# SERIAL_FMU3_REV_G.net
KiCad netlist of a schematic drawn in Altium Designer
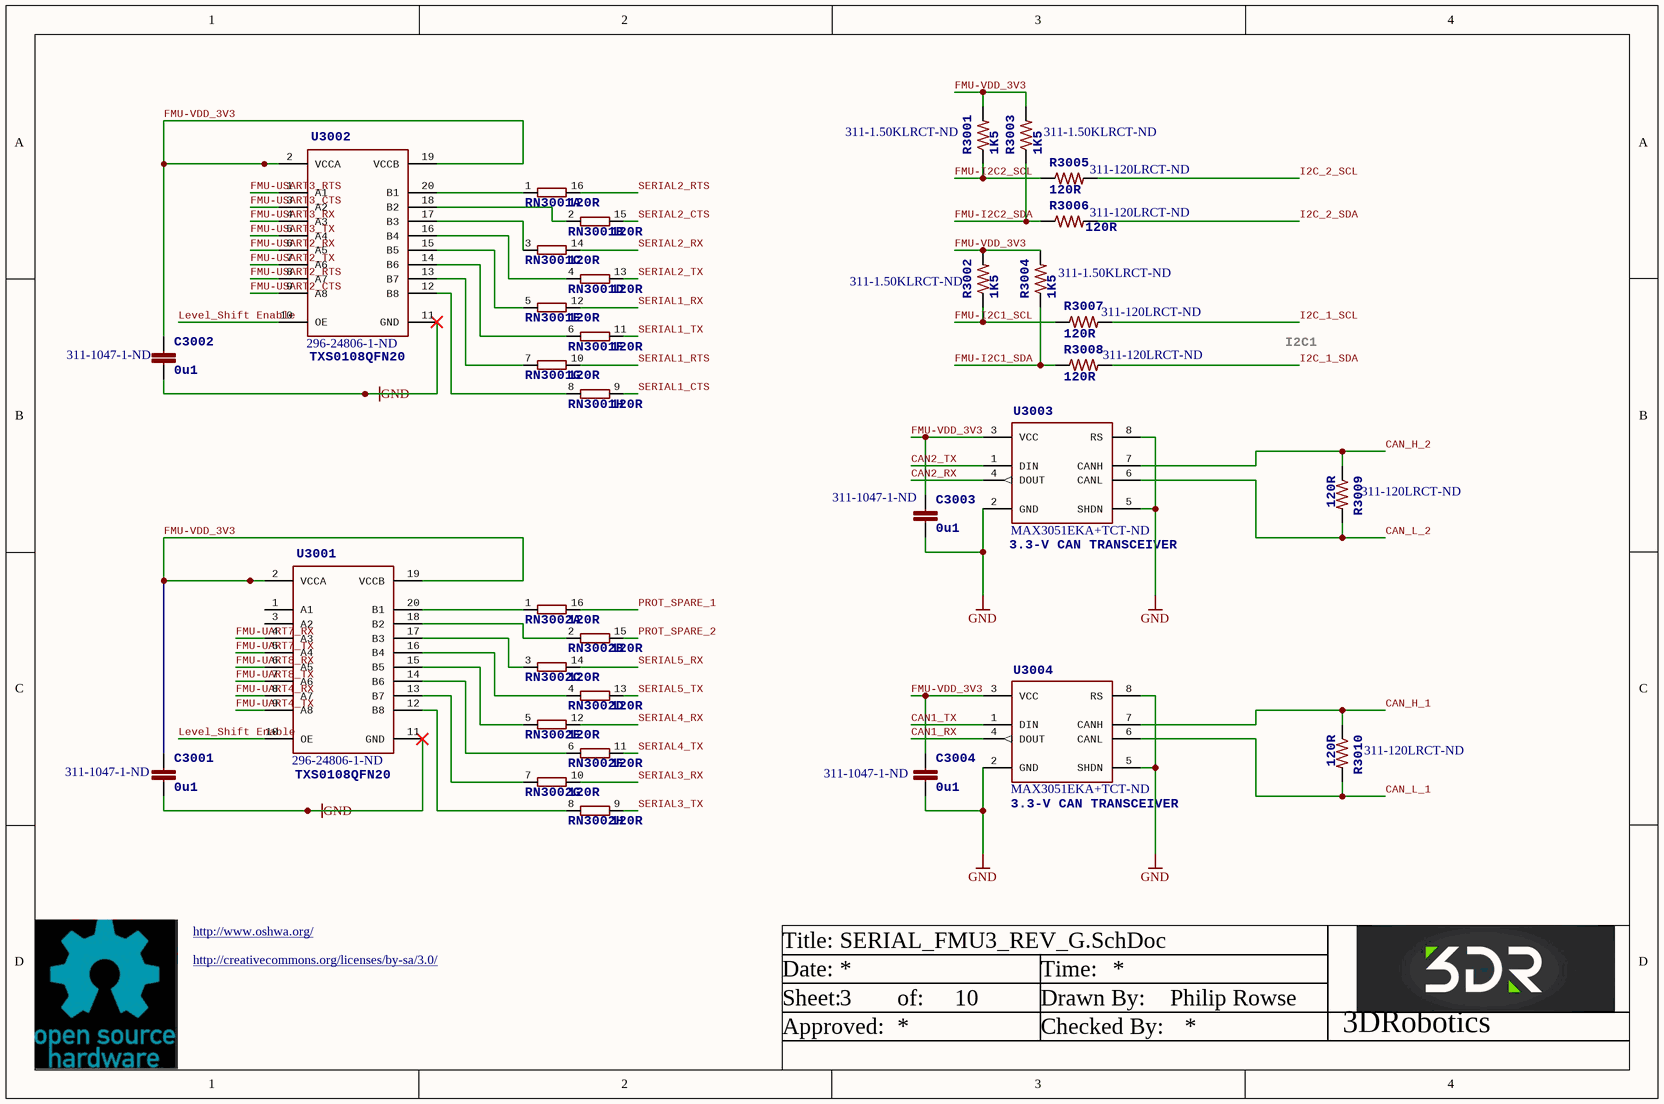
[diagram p0: SERIAL_FMU3_REV_G.SchDoc]

(export (version "E")
  (design (tool "Eeschema 10.0.6"))
  (components
    (comp (ref "C3001")
      (value "0u1")
      (footprint "0402-CAP")
      (description "CAP CER 0.1UF 16V Y5V 0402")
      (fields
        (field (name "PARTNO") "CC0402ZRY5V7BB104")
        (field (name "SUPPLIER PART NUMBER 1") "311-1047-1-ND")
        (field (name "3DR_PARTNO") "ECM0700")
      )
      (libsource (lib "pixhawk2") (part "CAP0402"))
    )
    (comp (ref "C3002")
      (value "0u1")
      (footprint "0402-CAP")
      (description "CAP CER 0.1UF 16V Y5V 0402")
      (fields
        (field (name "PARTNO") "CC0402ZRY5V7BB104")
        (field (name "SUPPLIER PART NUMBER 1") "311-1047-1-ND")
        (field (name "3DR_PARTNO") "ECM0700")
      )
      (libsource (lib "pixhawk2") (part "CAP0402"))
    )
    (comp (ref "C3003")
      (value "0u1")
      (footprint "0402-CAP")
      (description "CAP CER 0.1UF 16V Y5V 0402")
      (fields
        (field (name "PARTNO") "CC0402ZRY5V7BB104")
        (field (name "SUPPLIER PART NUMBER 1") "311-1047-1-ND")
        (field (name "3DR_PARTNO") "ECM0700")
      )
      (libsource (lib "pixhawk2") (part "CAP0402"))
    )
    (comp (ref "C3004")
      (value "0u1")
      (footprint "0402-CAP")
      (description "CAP CER 0.1UF 16V Y5V 0402")
      (fields
        (field (name "PARTNO") "CC0402ZRY5V7BB104")
        (field (name "SUPPLIER PART NUMBER 1") "311-1047-1-ND")
        (field (name "3DR_PARTNO") "ECM0700")
      )
      (libsource (lib "pixhawk2") (part "CAP0402"))
    )
    (comp (ref "R3001")
      (value "1K5")
      (footprint "0402-RES")
      (description "RES 1.5K OHM 1/16W 1% 0402 SMD")
      (fields
        (field (name "PARTNO") "RC0402FR-071K5L")
        (field (name "SUPPLIER PART NUMBER 1") "311-1.50KLRCT-ND")
        (field (name "3DR_PARTNO") "ECM0803")
      )
      (libsource (lib "pixhawk2") (part "RESISTOR0402-RES"))
    )
    (comp (ref "R3002")
      (value "1K5")
      (footprint "0402-RES")
      (description "RES 1.5K OHM 1/16W 1% 0402 SMD")
      (fields
        (field (name "PARTNO") "RC0402FR-071K5L")
        (field (name "SUPPLIER PART NUMBER 1") "311-1.50KLRCT-ND")
        (field (name "3DR_PARTNO") "ECM0803")
      )
      (libsource (lib "pixhawk2") (part "RESISTOR0402-RES"))
    )
    (comp (ref "R3003")
      (value "1K5")
      (footprint "0402-RES")
      (description "RES 1.5K OHM 1/16W 1% 0402 SMD")
      (fields
        (field (name "PARTNO") "RC0402FR-071K5L")
        (field (name "SUPPLIER PART NUMBER 1") "311-1.50KLRCT-ND")
        (field (name "3DR_PARTNO") "ECM0803")
      )
      (libsource (lib "pixhawk2") (part "RESISTOR0402-RES"))
    )
    (comp (ref "R3004")
      (value "1K5")
      (footprint "0402-RES")
      (description "RES 1.5K OHM 1/16W 1% 0402 SMD")
      (fields
        (field (name "PARTNO") "RC0402FR-071K5L")
        (field (name "SUPPLIER PART NUMBER 1") "311-1.50KLRCT-ND")
        (field (name "3DR_PARTNO") "ECM0803")
      )
      (libsource (lib "pixhawk2") (part "RESISTOR0402-RES"))
    )
    (comp (ref "R3005")
      (value "120R")
      (footprint "0402-RES")
      (description "RES 120 OHM 1/16W 1% 0402 SMD")
      (fields
        (field (name "PARTNO") "RC0402FR-07120RL")
        (field (name "SUPPLIER PART NUMBER 1") "311-120LRCT-ND")
        (field (name "3DR_PARTNO") "ECM0820")
      )
      (libsource (lib "pixhawk2") (part "RESISTOR0402-RES"))
    )
    (comp (ref "R3006")
      (value "120R")
      (footprint "0402-RES")
      (description "RES 120 OHM 1/16W 1% 0402 SMD")
      (fields
        (field (name "PARTNO") "RC0402FR-07120RL")
        (field (name "SUPPLIER PART NUMBER 1") "311-120LRCT-ND")
        (field (name "3DR_PARTNO") "ECM0820")
      )
      (libsource (lib "pixhawk2") (part "RESISTOR0402-RES"))
    )
    (comp (ref "R3007")
      (value "120R")
      (footprint "0402-RES")
      (description "RES 120 OHM 1/16W 1% 0402 SMD")
      (fields
        (field (name "PARTNO") "RC0402FR-07120RL")
        (field (name "SUPPLIER PART NUMBER 1") "311-120LRCT-ND")
        (field (name "3DR_PARTNO") "ECM0820")
      )
      (libsource (lib "pixhawk2") (part "RESISTOR0402-RES"))
    )
    (comp (ref "R3008")
      (value "120R")
      (footprint "0402-RES")
      (description "RES 120 OHM 1/16W 1% 0402 SMD")
      (fields
        (field (name "PARTNO") "RC0402FR-07120RL")
        (field (name "SUPPLIER PART NUMBER 1") "311-120LRCT-ND")
        (field (name "3DR_PARTNO") "ECM0820")
      )
      (libsource (lib "pixhawk2") (part "RESISTOR0402-RES"))
    )
    (comp (ref "R3009")
      (value "120R")
      (footprint "0402-RES")
      (description "RES 120 OHM 1/16W 1% 0402 SMD")
      (fields
        (field (name "PARTNO") "RC0402FR-07120RL")
        (field (name "SUPPLIER PART NUMBER 1") "311-120LRCT-ND")
        (field (name "3DR_PARTNO") "ECM0820")
      )
      (libsource (lib "pixhawk2") (part "RESISTOR0402-RES"))
    )
    (comp (ref "R3010")
      (value "120R")
      (footprint "0402-RES")
      (description "RES 120 OHM 1/16W 1% 0402 SMD")
      (fields
        (field (name "PARTNO") "RC0402FR-07120RL")
        (field (name "SUPPLIER PART NUMBER 1") "311-120LRCT-ND")
        (field (name "3DR_PARTNO") "ECM0820")
      )
      (libsource (lib "pixhawk2") (part "RESISTOR0402-RES"))
    )
    (comp (ref "RN3001")
      (value "120R")
      (footprint "EXB2HV")
      (description "RES ARRAY 120 OHM 8 RES 1506")
      (fields (field (name "PARTNO") "EXB-2HV121JV") (field (name "3DR_PARTNO") "EMC"))
      (libsource (lib "pixhawk2") (part "8R-NEXB2HV-120R"))
    )
    (comp (ref "RN3002")
      (value "120R")
      (footprint "EXB2HV")
      (description "RES ARRAY 120 OHM 8 RES 1506")
      (fields (field (name "PARTNO") "EXB-2HV121JV") (field (name "3DR_PARTNO") "EMC"))
      (libsource (lib "pixhawk2") (part "8R-NEXB2HV-120R"))
    )
    (comp (ref "U3001")
      (value "TXS0108QFN20")
      (footprint "QFN20-RGY")
      (description "IC XLATR VOLT-LVL 8B BDIR 20QFN")
      (fields
        (field (name "SUPPLIER PART NUMBER 1") "296-24806-1-ND")
        (field (name "3DR_PARTNO") "ECM0845")
        (field (name "PARTNO") "TXS0108ERGYR")
      )
      (libsource (lib "pixhawk2") (part "TXS0108QFN20"))
    )
    (comp (ref "U3002")
      (value "TXS0108QFN20")
      (footprint "QFN20-RGY")
      (description "IC XLATR VOLT-LVL 8B BDIR 20QFN")
      (fields
        (field (name "SUPPLIER PART NUMBER 1") "296-24806-1-ND")
        (field (name "3DR_PARTNO") "ECM0845")
        (field (name "PARTNO") "TXS0108ERGYR")
      )
      (libsource (lib "pixhawk2") (part "TXS0108QFN20"))
    )
    (comp (ref "U3003")
      (value "3.3-V CAN TRANSCEIVER")
      (footprint "SOT23-8")
      (description "IC TXRX CAN 1MBPS SOT23-8")
      (fields
        (field (name "SUPPLIER PART NUMBER 1") "MAX3051EKA+TCT-ND")
        (field (name "3DR_PARTNO") "ECM0831")
        (field (name "PARTNO") "MAX3051EKA+T")
      )
      (libsource (lib "pixhawk2") (part "MAX3051MAX3051EKA"))
    )
    (comp (ref "U3004")
      (value "3.3-V CAN TRANSCEIVER")
      (footprint "SOT23-8")
      (description "IC TXRX CAN 1MBPS SOT23-8")
      (fields
        (field (name "SUPPLIER PART NUMBER 1") "MAX3051EKA+TCT-ND")
        (field (name "3DR_PARTNO") "ECM0831")
        (field (name "PARTNO") "MAX3051EKA+T")
      )
      (libsource (lib "pixhawk2") (part "MAX3051MAX3051EKA"))
    )
  )
  (nets
    (net (code "1") (name "/CAN1_RX") (class "Default")
      (node (ref "U3004") (pin "4") (pinfunction "DOUT_4") (pintype "output"))
    )
    (net (code "2") (name "/CAN1_TX") (class "Default")
      (node (ref "U3004") (pin "1") (pinfunction "DIN_1") (pintype "passive"))
    )
    (net (code "3") (name "/CAN2_RX") (class "Default")
      (node (ref "U3003") (pin "4") (pinfunction "DOUT_4") (pintype "output"))
    )
    (net (code "4") (name "/CAN2_TX") (class "Default")
      (node (ref "U3003") (pin "1") (pinfunction "DIN_1") (pintype "passive"))
    )
    (net (code "5") (name "/CAN_H_1") (class "Default")
      (node (ref "R3010") (pin "P$1") (pinfunction "1_P$1") (pintype "passive"))
      (node (ref "U3004") (pin "7") (pinfunction "CANH_7") (pintype "passive"))
    )
    (net (code "6") (name "/CAN_H_2") (class "Default")
      (node (ref "R3009") (pin "P$1") (pinfunction "1_P$1") (pintype "passive"))
      (node (ref "U3003") (pin "7") (pinfunction "CANH_7") (pintype "passive"))
    )
    (net (code "7") (name "/CAN_L_1") (class "Default")
      (node (ref "R3010") (pin "P$2") (pinfunction "2_P$2") (pintype "passive"))
      (node (ref "U3004") (pin "6") (pinfunction "CANL_6") (pintype "passive"))
    )
    (net (code "8") (name "/CAN_L_2") (class "Default")
      (node (ref "R3009") (pin "P$2") (pinfunction "2_P$2") (pintype "passive"))
      (node (ref "U3003") (pin "6") (pinfunction "CANL_6") (pintype "passive"))
    )
    (net (code "9") (name "/FMU-I2C1_SCL") (class "Default")
      (node (ref "R3002") (pin "P$1") (pinfunction "1_P$1") (pintype "passive"))
      (node (ref "R3007") (pin "P$1") (pinfunction "1_P$1") (pintype "passive"))
    )
    (net (code "10") (name "/FMU-I2C1_SDA") (class "Default")
      (node (ref "R3004") (pin "P$1") (pinfunction "1_P$1") (pintype "passive"))
      (node (ref "R3008") (pin "P$1") (pinfunction "1_P$1") (pintype "passive"))
    )
    (net (code "11") (name "/FMU-I2C2_SCL") (class "Default")
      (node (ref "R3001") (pin "P$1") (pinfunction "1_P$1") (pintype "passive"))
      (node (ref "R3005") (pin "P$1") (pinfunction "1_P$1") (pintype "passive"))
    )
    (net (code "12") (name "/FMU-I2C2_SDA") (class "Default")
      (node (ref "R3003") (pin "P$1") (pinfunction "1_P$1") (pintype "passive"))
      (node (ref "R3006") (pin "P$1") (pinfunction "1_P$1") (pintype "passive"))
    )
    (net (code "13") (name "/FMU-UART4_RX") (class "Default")
      (node (ref "U3001") (pin "8") (pinfunction "A7_8") (pintype "passive"))
    )
    (net (code "14") (name "/FMU-UART4_TX") (class "Default")
      (node (ref "U3001") (pin "9") (pinfunction "A8_9") (pintype "passive"))
    )
    (net (code "15") (name "/FMU-UART7_RX") (class "Default")
      (node (ref "U3001") (pin "4") (pinfunction "A3_4") (pintype "passive"))
    )
    (net (code "16") (name "/FMU-UART7_TX") (class "Default")
      (node (ref "U3001") (pin "5") (pinfunction "A4_5") (pintype "passive"))
    )
    (net (code "17") (name "/FMU-UART8_RX") (class "Default")
      (node (ref "U3001") (pin "6") (pinfunction "A5_6") (pintype "passive"))
    )
    (net (code "18") (name "/FMU-UART8_TX") (class "Default")
      (node (ref "U3001") (pin "7") (pinfunction "A6_7") (pintype "passive"))
    )
    (net (code "19") (name "/FMU-USART2_CTS") (class "Default")
      (node (ref "U3002") (pin "9") (pinfunction "A8_9") (pintype "passive"))
    )
    (net (code "20") (name "/FMU-USART2_RTS") (class "Default")
      (node (ref "U3002") (pin "8") (pinfunction "A7_8") (pintype "passive"))
    )
    (net (code "21") (name "/FMU-USART2_RX") (class "Default")
      (node (ref "U3002") (pin "6") (pinfunction "A5_6") (pintype "passive"))
    )
    (net (code "22") (name "/FMU-USART2_TX") (class "Default")
      (node (ref "U3002") (pin "7") (pinfunction "A6_7") (pintype "passive"))
    )
    (net (code "23") (name "/FMU-USART3_CTS") (class "Default")
      (node (ref "U3002") (pin "3") (pinfunction "A2_3") (pintype "passive"))
    )
    (net (code "24") (name "/FMU-USART3_RTS") (class "Default")
      (node (ref "U3002") (pin "1") (pinfunction "A1_1") (pintype "passive"))
    )
    (net (code "25") (name "/FMU-USART3_RX") (class "Default")
      (node (ref "U3002") (pin "4") (pinfunction "A3_4") (pintype "passive"))
    )
    (net (code "26") (name "/FMU-USART3_TX") (class "Default")
      (node (ref "U3002") (pin "5") (pinfunction "A4_5") (pintype "passive"))
    )
    (net (code "27") (name "/FMU-VDD_3V3") (class "Default")
      (node (ref "C3001") (pin "P$1") (pinfunction "1_P$1") (pintype "passive"))
      (node (ref "C3002") (pin "P$1") (pinfunction "1_P$1") (pintype "passive"))
      (node (ref "C3003") (pin "P$1") (pinfunction "1_P$1") (pintype "passive"))
      (node (ref "C3004") (pin "P$1") (pinfunction "1_P$1") (pintype "passive"))
      (node (ref "R3001") (pin "P$2") (pinfunction "2_P$2") (pintype "passive"))
      (node (ref "R3002") (pin "P$2") (pinfunction "2_P$2") (pintype "passive"))
      (node (ref "R3003") (pin "P$2") (pinfunction "2_P$2") (pintype "passive"))
      (node (ref "R3004") (pin "P$2") (pinfunction "2_P$2") (pintype "passive"))
      (node (ref "U3001") (pin "19") (pinfunction "VCCB_19") (pintype "passive"))
      (node (ref "U3001") (pin "2") (pinfunction "VCCA_2") (pintype "passive"))
      (node (ref "U3002") (pin "19") (pinfunction "VCCB_19") (pintype "passive"))
      (node (ref "U3002") (pin "2") (pinfunction "VCCA_2") (pintype "passive"))
      (node (ref "U3003") (pin "3") (pinfunction "VCC_3") (pintype "passive"))
      (node (ref "U3004") (pin "3") (pinfunction "VCC_3") (pintype "passive"))
    )
    (net (code "28") (name "/I2C_1_SCL") (class "Default")
      (node (ref "R3007") (pin "P$2") (pinfunction "2_P$2") (pintype "passive"))
    )
    (net (code "29") (name "/I2C_1_SDA") (class "Default")
      (node (ref "R3008") (pin "P$2") (pinfunction "2_P$2") (pintype "passive"))
    )
    (net (code "30") (name "/I2C_2_SCL") (class "Default")
      (node (ref "R3005") (pin "P$2") (pinfunction "2_P$2") (pintype "passive"))
    )
    (net (code "31") (name "/I2C_2_SDA") (class "Default")
      (node (ref "R3006") (pin "P$2") (pinfunction "2_P$2") (pintype "passive"))
    )
    (net (code "32") (name "/Level_Shift Enable") (class "Default")
      (node (ref "U3001") (pin "10") (pinfunction "OE_10") (pintype "passive"))
      (node (ref "U3002") (pin "10") (pinfunction "OE_10") (pintype "passive"))
    )
    (net (code "33") (name "/PROT_SPARE_1") (class "Default")
      (node (ref "RN3002") (pin "16") (pinfunction "2_16") (pintype "passive"))
    )
    (net (code "34") (name "/PROT_SPARE_2") (class "Default")
      (node (ref "RN3002") (pin "15") (pinfunction "2_15") (pintype "passive"))
    )
    (net (code "35") (name "/SERIAL1_CTS") (class "Default")
      (node (ref "RN3001") (pin "9") (pinfunction "2_9") (pintype "passive"))
    )
    (net (code "36") (name "/SERIAL1_RTS") (class "Default")
      (node (ref "RN3001") (pin "10") (pinfunction "2_10") (pintype "passive"))
    )
    (net (code "37") (name "/SERIAL1_RX") (class "Default")
      (node (ref "RN3001") (pin "12") (pinfunction "2_12") (pintype "passive"))
    )
    (net (code "38") (name "/SERIAL1_TX") (class "Default")
      (node (ref "RN3001") (pin "11") (pinfunction "2_11") (pintype "passive"))
    )
    (net (code "39") (name "/SERIAL2_CTS") (class "Default")
      (node (ref "RN3001") (pin "15") (pinfunction "2_15") (pintype "passive"))
    )
    (net (code "40") (name "/SERIAL2_RTS") (class "Default")
      (node (ref "RN3001") (pin "16") (pinfunction "2_16") (pintype "passive"))
    )
    (net (code "41") (name "/SERIAL2_RX") (class "Default")
      (node (ref "RN3001") (pin "14") (pinfunction "2_14") (pintype "passive"))
    )
    (net (code "42") (name "/SERIAL2_TX") (class "Default")
      (node (ref "RN3001") (pin "13") (pinfunction "2_13") (pintype "passive"))
    )
    (net (code "43") (name "/SERIAL3_RX") (class "Default")
      (node (ref "RN3002") (pin "10") (pinfunction "2_10") (pintype "passive"))
    )
    (net (code "44") (name "/SERIAL3_TX") (class "Default")
      (node (ref "RN3002") (pin "9") (pinfunction "2_9") (pintype "passive"))
    )
    (net (code "45") (name "/SERIAL4_RX") (class "Default")
      (node (ref "RN3002") (pin "12") (pinfunction "2_12") (pintype "passive"))
    )
    (net (code "46") (name "/SERIAL4_TX") (class "Default")
      (node (ref "RN3002") (pin "11") (pinfunction "2_11") (pintype "passive"))
    )
    (net (code "47") (name "/SERIAL5_RX") (class "Default")
      (node (ref "RN3002") (pin "14") (pinfunction "2_14") (pintype "passive"))
    )
    (net (code "48") (name "/SERIAL5_TX") (class "Default")
      (node (ref "RN3002") (pin "13") (pinfunction "2_13") (pintype "passive"))
    )
    (net (code "49") (name "GND") (class "Default")
      (node (ref "C3001") (pin "P$2") (pinfunction "2_P$2") (pintype "passive"))
      (node (ref "C3002") (pin "P$2") (pinfunction "2_P$2") (pintype "passive"))
      (node (ref "C3003") (pin "P$2") (pinfunction "2_P$2") (pintype "passive"))
      (node (ref "C3004") (pin "P$2") (pinfunction "2_P$2") (pintype "passive"))
      (node (ref "U3001") (pin "11") (pinfunction "GND_11") (pintype "open_emitter"))
      (node (ref "U3002") (pin "11") (pinfunction "GND_11") (pintype "open_emitter"))
      (node (ref "U3003") (pin "2") (pinfunction "GND_2") (pintype "open_emitter"))
      (node (ref "U3003") (pin "5") (pinfunction "SHDN_5") (pintype "passive"))
      (node (ref "U3003") (pin "8") (pinfunction "RS_8") (pintype "passive"))
      (node (ref "U3004") (pin "2") (pinfunction "GND_2") (pintype "open_emitter"))
      (node (ref "U3004") (pin "5") (pinfunction "SHDN_5") (pintype "passive"))
      (node (ref "U3004") (pin "8") (pinfunction "RS_8") (pintype "passive"))
    )
    (net (code "50") (name "Net-(RN3001B-1)") (class "Default")
      (node (ref "RN3001") (pin "2") (pinfunction "1_2") (pintype "passive"))
      (node (ref "U3002") (pin "18") (pinfunction "B2_18") (pintype "passive"))
    )
    (net (code "51") (name "Net-(RN3001C-1)") (class "Default")
      (node (ref "RN3001") (pin "3") (pinfunction "1_3") (pintype "passive"))
      (node (ref "U3002") (pin "17") (pinfunction "B3_17") (pintype "passive"))
    )
    (net (code "52") (name "Net-(RN3001D-1)") (class "Default")
      (node (ref "RN3001") (pin "4") (pinfunction "1_4") (pintype "passive"))
      (node (ref "U3002") (pin "16") (pinfunction "B4_16") (pintype "passive"))
    )
    (net (code "53") (name "Net-(RN3001E-1)") (class "Default")
      (node (ref "RN3001") (pin "5") (pinfunction "1_5") (pintype "passive"))
      (node (ref "U3002") (pin "15") (pinfunction "B5_15") (pintype "passive"))
    )
    (net (code "54") (name "Net-(RN3001F-1)") (class "Default")
      (node (ref "RN3001") (pin "6") (pinfunction "1_6") (pintype "passive"))
      (node (ref "U3002") (pin "14") (pinfunction "B6_14") (pintype "passive"))
    )
    (net (code "55") (name "Net-(RN3001G-1)") (class "Default")
      (node (ref "RN3001") (pin "7") (pinfunction "1_7") (pintype "passive"))
      (node (ref "U3002") (pin "13") (pinfunction "B7_13") (pintype "passive"))
    )
    (net (code "56") (name "Net-(RN3001H-1)") (class "Default")
      (node (ref "RN3001") (pin "8") (pinfunction "1_8") (pintype "passive"))
      (node (ref "U3002") (pin "12") (pinfunction "B8_12") (pintype "passive"))
    )
    (net (code "57") (name "Net-(RN3002B-1)") (class "Default")
      (node (ref "RN3002") (pin "2") (pinfunction "1_2") (pintype "passive"))
      (node (ref "U3001") (pin "18") (pinfunction "B2_18") (pintype "passive"))
    )
    (net (code "58") (name "Net-(RN3002C-1)") (class "Default")
      (node (ref "RN3002") (pin "3") (pinfunction "1_3") (pintype "passive"))
      (node (ref "U3001") (pin "17") (pinfunction "B3_17") (pintype "passive"))
    )
    (net (code "59") (name "Net-(RN3002D-1)") (class "Default")
      (node (ref "RN3002") (pin "4") (pinfunction "1_4") (pintype "passive"))
      (node (ref "U3001") (pin "16") (pinfunction "B4_16") (pintype "passive"))
    )
    (net (code "60") (name "Net-(RN3002E-1)") (class "Default")
      (node (ref "RN3002") (pin "5") (pinfunction "1_5") (pintype "passive"))
      (node (ref "U3001") (pin "15") (pinfunction "B5_15") (pintype "passive"))
    )
    (net (code "61") (name "Net-(RN3002F-1)") (class "Default")
      (node (ref "RN3002") (pin "6") (pinfunction "1_6") (pintype "passive"))
      (node (ref "U3001") (pin "14") (pinfunction "B6_14") (pintype "passive"))
    )
    (net (code "62") (name "Net-(RN3002G-1)") (class "Default")
      (node (ref "RN3002") (pin "7") (pinfunction "1_7") (pintype "passive"))
      (node (ref "U3001") (pin "13") (pinfunction "B7_13") (pintype "passive"))
    )
    (net (code "63") (name "Net-(RN3002H-1)") (class "Default")
      (node (ref "RN3002") (pin "8") (pinfunction "1_8") (pintype "passive"))
      (node (ref "U3001") (pin "12") (pinfunction "B8_12") (pintype "passive"))
    )
    (net (code "64") (name "Net-(U3001-B1)") (class "Default")
      (node (ref "RN3002") (pin "1") (pinfunction "1_1") (pintype "passive"))
      (node (ref "U3001") (pin "20") (pinfunction "B1_20") (pintype "passive"))
    )
    (net (code "65") (name "Net-(U3002-B1)") (class "Default")
      (node (ref "RN3001") (pin "1") (pinfunction "1_1") (pintype "passive"))
      (node (ref "U3002") (pin "20") (pinfunction "B1_20") (pintype "passive"))
    )
    (net (code "66") (name "unconnected-(U3001-A1-Pad1)") (class "Default")
      (node (ref "U3001") (pin "1") (pinfunction "A1_1") (pintype "passive"))
    )
    (net (code "67") (name "unconnected-(U3001-A2-Pad3)") (class "Default")
      (node (ref "U3001") (pin "3") (pinfunction "A2_3") (pintype "passive"))
    )
  )
)
